# wikiduino-atmega328p.net
KiCad netlist of a schematic drawn in Altium Designer
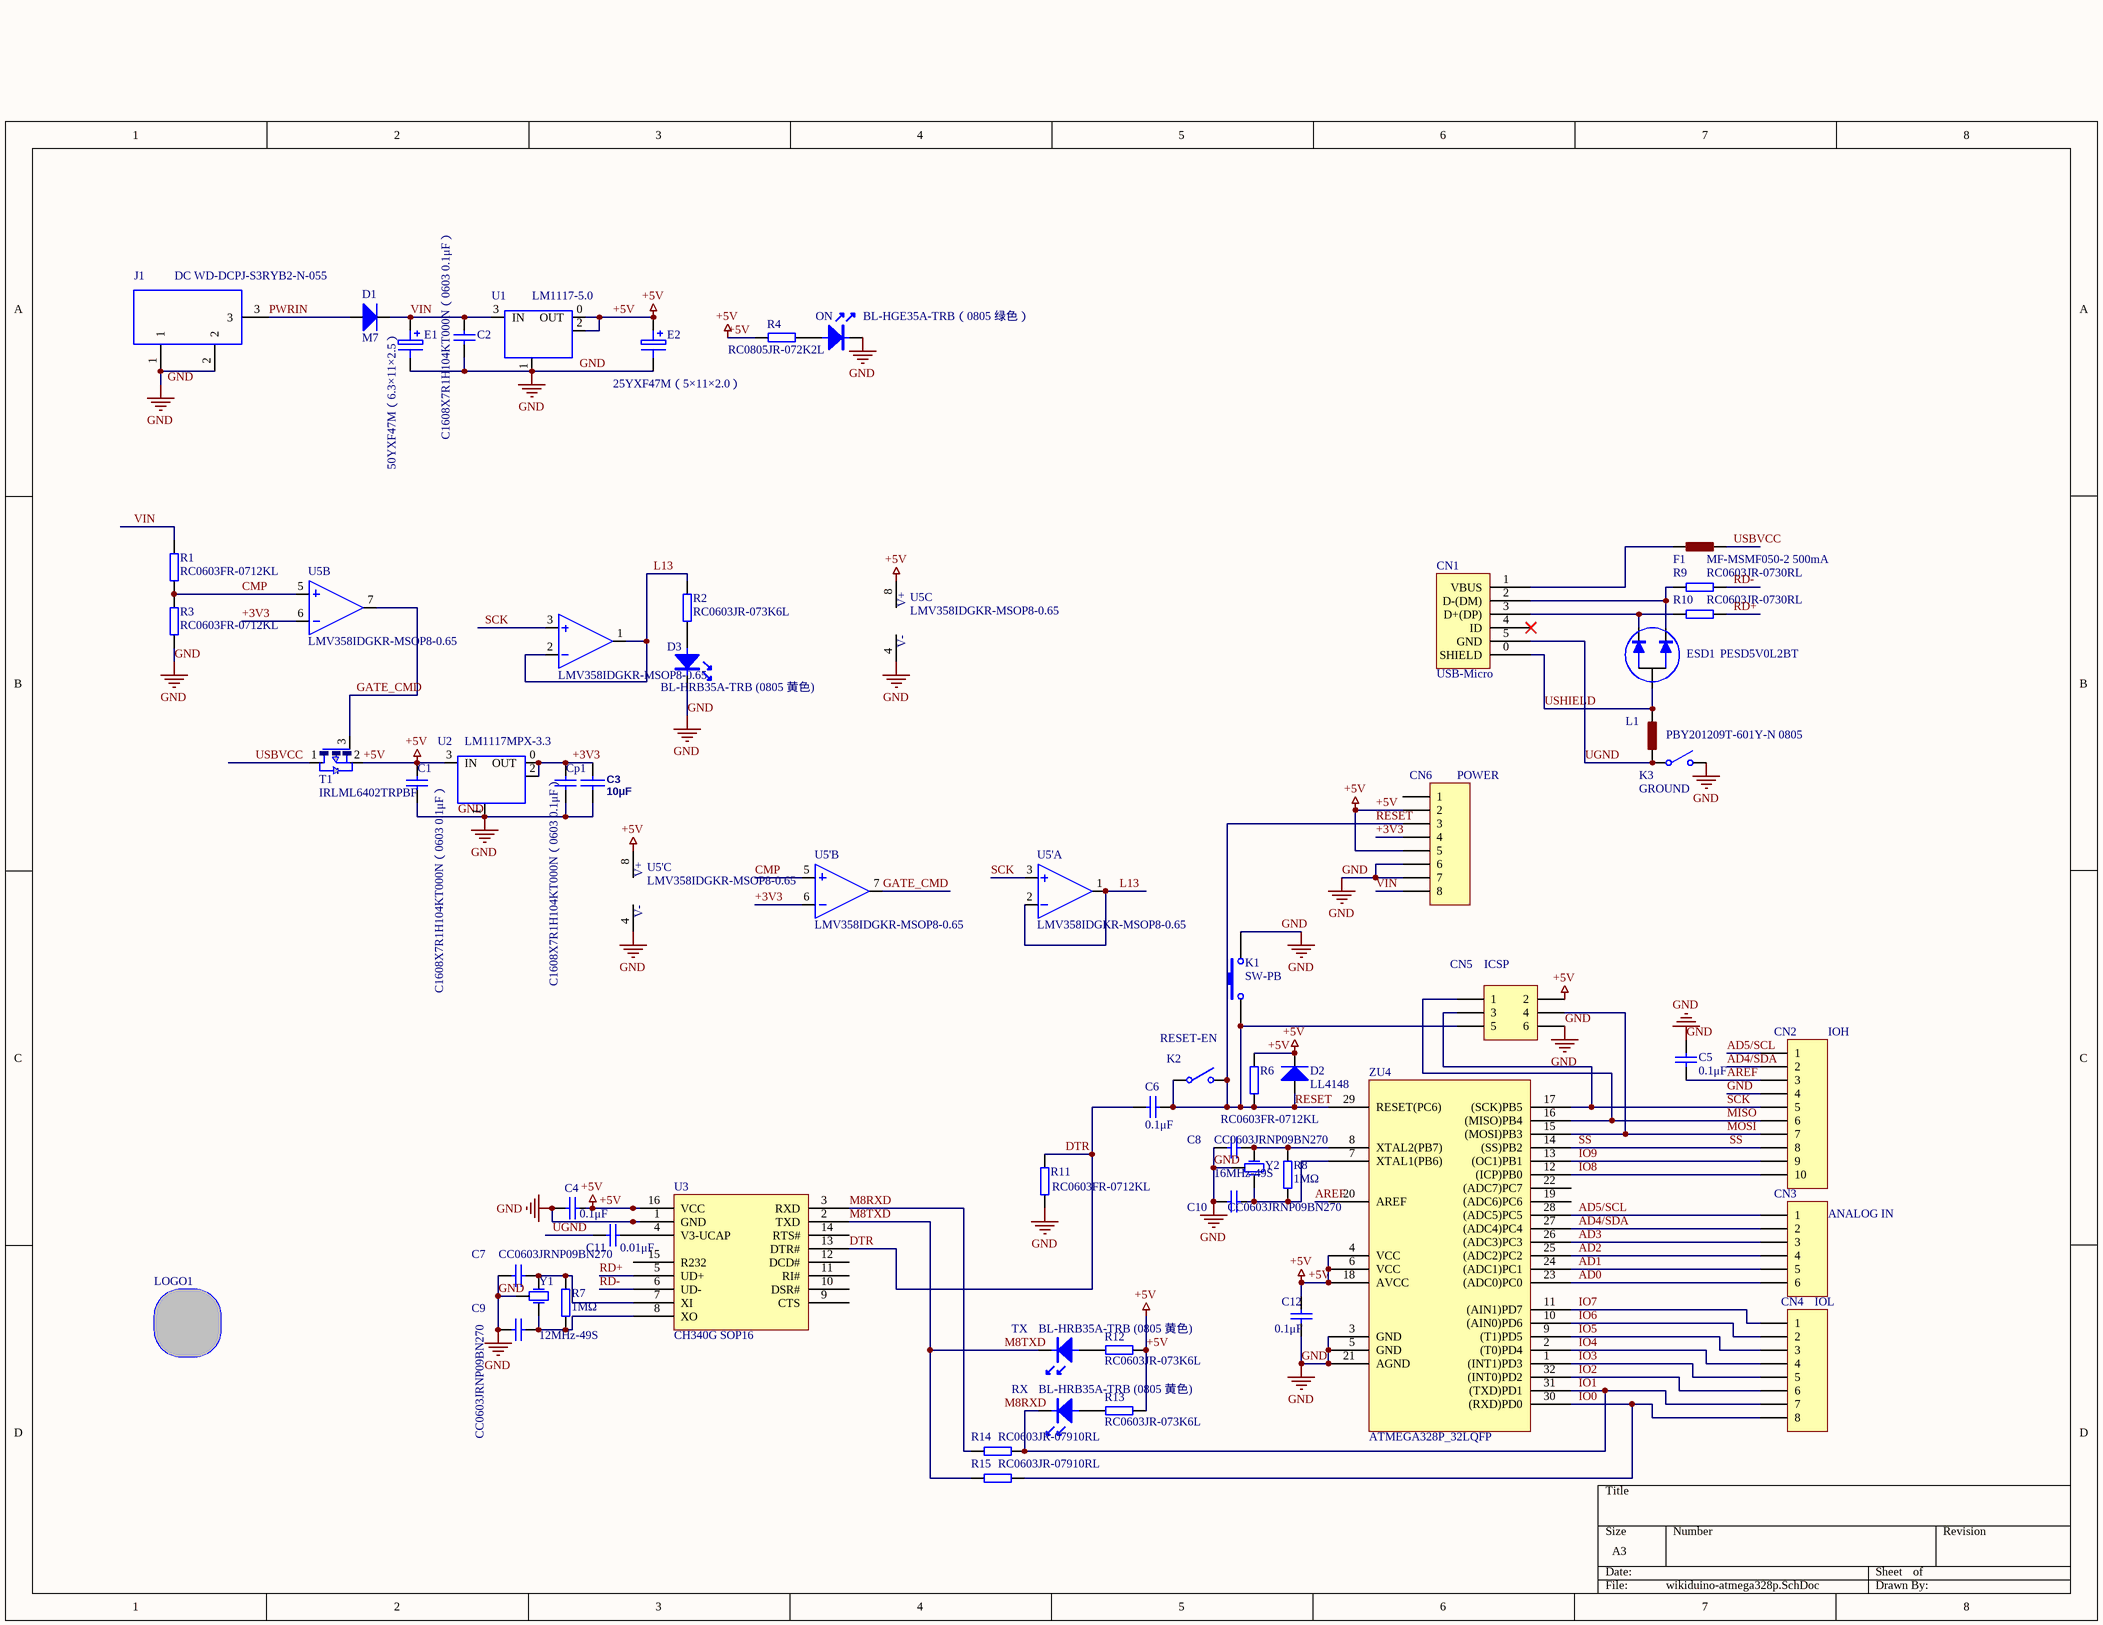
[diagram p0: wikiduino-atmega328p.SchDoc]

(export (version "E")
  (design (tool "Eeschema 10.0.6"))
  (components
    (comp (ref "C1")
      (value "C1608X7R1H104KT000N（0603 0.1μF）")
      (footprint "0603C")
      (description "Capacitor")
      (fields (field (name "PUBLISHER") "Altium Limited"))
      (libsource (lib "*") (part "Cap"))
    )
    (comp (ref "C2")
      (value "C1608X7R1H104KT000N（0603 0.1μF）")
      (footprint "0603C")
      (description "Capacitor")
      (fields (field (name "PUBLISHER") "Altium Limited"))
      (libsource (lib "Miscellaneous Devices") (part "Cap"))
    )
    (comp (ref "C3")
      (value "10μF")
      (footprint "1206C")
      (description "Capacitor")
      (libsource (lib "*") (part "CAP"))
    )
    (comp (ref "C4")
      (value "0.1μF")
      (footprint "0603C")
      (description "Capacitor")
      (fields (field (name "PUBLISHER") "Altium Limited"))
      (libsource (lib "Miscellaneous Devices") (part "Cap"))
    )
    (comp (ref "C5")
      (value "0.1μF")
      (footprint "0603C")
      (description "Capacitor")
      (fields (field (name "PUBLISHER") "Altium Limited"))
      (libsource (lib "Miscellaneous Devices") (part "Cap"))
    )
    (comp (ref "C6")
      (value "0.1μF")
      (footprint "0603C")
      (description "Capacitor")
      (fields (field (name "PUBLISHER") "Altium Limited"))
      (libsource (lib "Miscellaneous Devices") (part "Cap"))
    )
    (comp (ref "C7")
      (value "CC0603JRNP09BN270")
      (footprint "0603C")
      (description "Capacitor")
      (fields (field (name "PUBLISHER") "Altium Limited"))
      (libsource (lib "Miscellaneous Devices") (part "Cap"))
    )
    (comp (ref "C8")
      (value "CC0603JRNP09BN270")
      (footprint "0603C")
      (description "Capacitor")
      (fields (field (name "PUBLISHER") "Altium Limited"))
      (libsource (lib "Miscellaneous Devices") (part "Cap"))
    )
    (comp (ref "C9")
      (value "CC0603JRNP09BN270")
      (footprint "0603C")
      (description "Capacitor")
      (fields (field (name "PUBLISHER") "Altium Limited"))
      (libsource (lib "Miscellaneous Devices") (part "Cap"))
    )
    (comp (ref "C10")
      (value "CC0603JRNP09BN270")
      (footprint "0603C")
      (description "Capacitor")
      (fields (field (name "PUBLISHER") "Altium Limited"))
      (libsource (lib "Miscellaneous Devices") (part "Cap"))
    )
    (comp (ref "C11")
      (value "0.01μF")
      (footprint "0603C")
      (description "Capacitor")
      (fields (field (name "PUBLISHER") "Altium Limited"))
      (libsource (lib "Miscellaneous Devices") (part "Cap"))
    )
    (comp (ref "C12")
      (value "0.1μF")
      (footprint "0603C")
      (description "Capacitor")
      (fields (field (name "PUBLISHER") "Altium Limited"))
      (libsource (lib "Miscellaneous Devices") (part "Cap"))
    )
    (comp (ref "CN1")
      (value "USB-Micro")
      (footprint "USB_MICRO_5S_B")
      (libsource (lib "Connector") (part "USB-Micro"))
    )
    (comp (ref "CN2")
      (value "IOH")
      (footprint "HDR1X10Z")
      (description "Header, 10-Pin")
      (fields (field (name "PUBLISHER") "Altium Limited"))
      (libsource (lib "Miscellaneous Connectors") (part "Header 10"))
    )
    (comp (ref "CN3")
      (value "ANALOG IN")
      (footprint "HDR1X6Z")
      (description "Header, 6-Pin")
      (fields (field (name "PUBLISHER") "Altium Limited"))
      (libsource (lib "Miscellaneous Connectors") (part "Header 6"))
    )
    (comp (ref "CN4")
      (value "IOL")
      (footprint "HDR1X8Z")
      (description "Header, 8-Pin")
      (fields (field (name "PUBLISHER") "Altium Limited"))
      (libsource (lib "Miscellaneous Connectors") (part "Header 8"))
    )
    (comp (ref "CN5")
      (value "ICSP")
      (footprint "HDR2X3")
      (description "Header, 3-Pin, Dual row")
      (fields (field (name "PUBLISHER") "Altium Limited"))
      (libsource (lib "Miscellaneous Connectors") (part "Header 3X2"))
    )
    (comp (ref "CN6")
      (value "POWER")
      (footprint "HDR1X8Z")
      (description "Header, 8-Pin")
      (fields (field (name "PUBLISHER") "Altium Limited"))
      (libsource (lib "Miscellaneous Connectors") (part "Header 8"))
    )
    (comp (ref "Cp1")
      (value "C1608X7R1H104KT000N（0603 0.1μF）")
      (footprint "0603C")
      (description "Capacitor")
      (fields (field (name "PUBLISHER") "Altium Limited"))
      (libsource (lib "*") (part "Cap"))
    )
    (comp (ref "D1")
      (value "M7")
      (footprint "M7")
      (description "D")
      (libsource (lib "Miscellaneous Devices") (part "M7"))
    )
    (comp (ref "D2")
      (value "LL4148")
      (footprint "D1206")
      (description "D")
      (libsource (lib "Miscellaneous Devices") (part "M7"))
    )
    (comp (ref "D3")
      (value "BL-HRB35A-TRB (0805 黄色)")
      (footprint "LED0805-Y")
      (libsource (lib "Miscellaneous Devices") (part "LED"))
    )
    (comp (ref "E1")
      (value "50YXF47M（6.3×11×2.5）")
      (footprint "RB 6.3×11×2.5")
      (libsource (lib "Miscellaneous Devices") (part "E"))
    )
    (comp (ref "E2")
      (value "25YXF47M（5×11×2.0）")
      (footprint "RB 6.3×11×2.5")
      (libsource (lib "Miscellaneous Devices") (part "E"))
    )
    (comp (ref "ESD1")
      (value "PESD5V0L2BT")
      (footprint "SOT-23")
      (libsource (lib "Miscellaneous Devices") (part "ESD1"))
    )
    (comp (ref "F1")
      (value "MF-MSMF050-2 500mA")
      (footprint "L1206")
      (description "BLM21")
      (libsource (lib "") (part "L_1"))
    )
    (comp (ref "J1")
      (value "DC WD-DCPJ-S3RYB2-N-055")
      (footprint "DC_IN")
      (description "POWERSUPPLY_DC21MMX")
      (libsource (lib "Miscellaneous Connectors") (part "DC_IN"))
    )
    (comp (ref "K1")
      (value "SW-PB")
      (footprint "按钮/SO")
      (description "Switch")
      (fields (field (name "PUBLISHER") "Altium Limited"))
      (libsource (lib "Miscellaneous Devices") (part "SW-PB"))
    )
    (comp (ref "K2")
      (value "RESET-EN")
      (footprint "0101")
      (description "Single-Pole, Single-Throw Switch")
      (fields (field (name "PUBLISHER") "Altium Limited"))
      (libsource (lib "Miscellaneous Devices") (part "SW-SPST"))
    )
    (comp (ref "K3")
      (value "GROUND")
      (footprint "0101")
      (description "Single-Pole, Single-Throw Switch")
      (fields (field (name "PUBLISHER") "Altium Limited"))
      (libsource (lib "Miscellaneous Devices") (part "SW-SPST"))
    )
    (comp (ref "L1")
      (value "PBY201209T-601Y-N 0805")
      (footprint "L0805")
      (description "BLM21")
      (libsource (lib "Miscellaneous Devices") (part "L"))
    )
    (comp (ref "LOGO1")
      (value "LOGO")
      (footprint "USB_LOGO")
      (libsource (lib "Miscellaneous Connectors") (part "LOGO"))
    )
    (comp (ref "ON")
      (value "BL-HGE35A-TRB（0805 绿色）")
      (footprint "LED0805-R")
      (libsource (lib "Miscellaneous Devices") (part "LED"))
    )
    (comp (ref "R1")
      (value "RC0603FR-0712KL")
      (footprint "0603R")
      (description "Resistor")
      (libsource (lib "Miscellaneous Devices") (part "R"))
    )
    (comp (ref "R2")
      (value "RC0603JR-073K6L")
      (footprint "0603R")
      (description "Resistor")
      (libsource (lib "Miscellaneous Devices") (part "R"))
    )
    (comp (ref "R3")
      (value "RC0603FR-0712KL")
      (footprint "0603R")
      (description "Resistor")
      (libsource (lib "Miscellaneous Devices") (part "R"))
    )
    (comp (ref "R4")
      (value "RC0805JR-072K2L")
      (footprint "0805/R")
      (description "Resistor")
      (libsource (lib "Miscellaneous Devices") (part "R"))
    )
    (comp (ref "R6")
      (value "RC0603FR-0712KL")
      (footprint "0603R")
      (description "Resistor")
      (libsource (lib "Miscellaneous Devices") (part "R"))
    )
    (comp (ref "R7")
      (value "1MΩ")
      (footprint "0603R")
      (description "Resistor")
      (libsource (lib "Miscellaneous Devices") (part "R"))
    )
    (comp (ref "R8")
      (value "1MΩ")
      (footprint "0603R")
      (description "Resistor")
      (libsource (lib "Miscellaneous Devices") (part "R"))
    )
    (comp (ref "R9")
      (value "RC0603JR-0730RL")
      (footprint "0603R")
      (description "Resistor")
      (libsource (lib "Miscellaneous Devices") (part "R"))
    )
    (comp (ref "R10")
      (value "RC0603JR-0730RL")
      (footprint "0603R")
      (description "Resistor")
      (libsource (lib "Miscellaneous Devices") (part "R"))
    )
    (comp (ref "R11")
      (value "RC0603FR-0712KL")
      (footprint "0603R")
      (description "Resistor")
      (libsource (lib "Miscellaneous Devices") (part "R"))
    )
    (comp (ref "R12")
      (value "RC0603JR-073K6L")
      (footprint "0603R")
      (description "Resistor")
      (libsource (lib "Miscellaneous Devices") (part "R"))
    )
    (comp (ref "R13")
      (value "RC0603JR-073K6L")
      (footprint "0603R")
      (description "Resistor")
      (libsource (lib "Miscellaneous Devices") (part "R"))
    )
    (comp (ref "R14")
      (value "RC0603JR-07910RL")
      (footprint "0603R")
      (description "Resistor")
      (libsource (lib "Miscellaneous Devices") (part "R"))
    )
    (comp (ref "R15")
      (value "RC0603JR-07910RL")
      (footprint "0603R")
      (description "Resistor")
      (libsource (lib "Miscellaneous Devices") (part "R"))
    )
    (comp (ref "RX")
      (value "BL-HRB35A-TRB (0805 黄色)")
      (footprint "LED0805-Y")
      (libsource (lib "Miscellaneous Devices") (part "LED"))
    )
    (comp (ref "T1")
      (value "IRLML6402TRPBF")
      (footprint "MOSFET")
      (libsource (lib "Miscellaneous Devices") (part "PMOSSOT23"))
    )
    (comp (ref "TX")
      (value "BL-HRB35A-TRB (0805 黄色)")
      (footprint "LED0805-Y")
      (libsource (lib "Miscellaneous Devices") (part "LED"))
    )
    (comp (ref "U1")
      (value "LM1117-5.0")
      (footprint "SOT223")
      (libsource (lib "Miscellaneous Devices") (part "LM1117"))
    )
    (comp (ref "U2")
      (value "LM1117MPX-3.3")
      (footprint "SOT223")
      (libsource (lib "Miscellaneous Devices") (part "LM1117"))
    )
    (comp (ref "U3")
      (value "CH340G SOP16")
      (footprint "SO-16")
      (libsource (lib "Miscellaneous Devices") (part "CH340G"))
    )
    (comp (ref "U5")
      (value "LMV358IDGKR-MSOP8-0.65")
      (footprint "MSOP8-0.65")
      (libsource (lib "wikiduino-atmega328p") (part "LMV358MMX"))
    )
    (comp (ref "U5'")
      (value "LMV358IDGKR-MSOP8-0.65")
      (footprint "so-8")
      (libsource (lib "wikiduino-atmega328p") (part "LMV358MMX"))
    )
    (comp (ref "Y1")
      (value "12MHz-49S")
      (footprint "XTAL-49S")
      (description "3pXTAL")
      (libsource (lib "Miscellaneous Devices") (part "XTAL1"))
    )
    (comp (ref "Y2")
      (value "16MHz-49S")
      (footprint "XTAL-49S")
      (description "3pXTAL")
      (libsource (lib "Miscellaneous Devices") (part "XTAL1"))
    )
    (comp (ref "ZU4")
      (value "ATMEGA328P_32LQFP")
      (footprint "LQFP32")
      (description "Arduino ATMEGA328P")
      (libsource (lib "Miscellaneous Devices") (part "ATMEGA328P_32LQFP"))
    )
  )
  (nets
    (net (code "1") (name "+5V") (class "Default")
      (node (ref "C1") (pin "1") (pinfunction "1_1") (pintype "passive"))
      (node (ref "C12") (pin "2") (pinfunction "2_2") (pintype "passive"))
      (node (ref "C4") (pin "2") (pinfunction "2_2") (pintype "passive"))
      (node (ref "CN5") (pin "2") (pinfunction "2_2") (pintype "passive"))
      (node (ref "CN6") (pin "2") (pinfunction "2_2") (pintype "passive"))
      (node (ref "CN6") (pin "5") (pinfunction "5_5") (pintype "passive"))
      (node (ref "D2") (pin "K") (pinfunction "K_K") (pintype "passive"))
      (node (ref "E2") (pin "1") (pintype "passive"))
      (node (ref "R12") (pin "1") (pintype "passive"))
      (node (ref "R13") (pin "1") (pintype "passive"))
      (node (ref "R4") (pin "2") (pintype "passive"))
      (node (ref "R6") (pin "1") (pintype "passive"))
      (node (ref "T1") (pin "2") (pinfunction "S_2") (pintype "passive"))
      (node (ref "U1") (pin "0") (pinfunction "OUT_0") (pintype "passive"))
      (node (ref "U1") (pin "2") (pinfunction "OUT@1_2") (pintype "passive"))
      (node (ref "U2") (pin "3") (pinfunction "IN_3") (pintype "passive"))
      (node (ref "U3") (pin "16") (pinfunction "VCC_16") (pintype "passive"))
      (node (ref "U5") (pin "8") (pinfunction "V+_8") (pintype "passive"))
      (node (ref "U5'") (pin "8") (pinfunction "V+_8") (pintype "passive"))
      (node (ref "ZU4") (pin "18") (pinfunction "AVCC_18") (pintype "passive"))
      (node (ref "ZU4") (pin "4") (pinfunction "VCC_4") (pintype "passive"))
      (node (ref "ZU4") (pin "6") (pinfunction "VCC_6") (pintype "passive"))
    )
    (net (code "2") (name "/+3V3") (class "Default")
      (node (ref "C3") (pin "2") (pinfunction "2_2") (pintype "passive"))
      (node (ref "CN6") (pin "4") (pinfunction "4_4") (pintype "passive"))
      (node (ref "Cp1") (pin "1") (pinfunction "1_1") (pintype "passive"))
      (node (ref "U2") (pin "0") (pinfunction "OUT_0") (pintype "passive"))
      (node (ref "U2") (pin "2") (pinfunction "OUT@1_2") (pintype "passive"))
      (node (ref "U5") (pin "6") (pinfunction "-IN_6") (pintype "passive"))
      (node (ref "U5'") (pin "6") (pinfunction "-IN_6") (pintype "passive"))
    )
    (net (code "3") (name "/AD0") (class "Default")
      (node (ref "CN3") (pin "6") (pinfunction "6_6") (pintype "passive"))
      (node (ref "ZU4") (pin "23") (pinfunction "(ADC0)PC0_23") (pintype "passive"))
    )
    (net (code "4") (name "/AD1") (class "Default")
      (node (ref "CN3") (pin "5") (pinfunction "5_5") (pintype "passive"))
      (node (ref "ZU4") (pin "24") (pinfunction "(ADC1)PC1_24") (pintype "passive"))
    )
    (net (code "5") (name "/AD2") (class "Default")
      (node (ref "CN3") (pin "4") (pinfunction "4_4") (pintype "passive"))
      (node (ref "ZU4") (pin "25") (pinfunction "(ADC2)PC2_25") (pintype "passive"))
    )
    (net (code "6") (name "/AD3") (class "Default")
      (node (ref "CN3") (pin "3") (pinfunction "3_3") (pintype "passive"))
      (node (ref "ZU4") (pin "26") (pinfunction "(ADC3)PC3_26") (pintype "passive"))
    )
    (net (code "7") (name "/AD4{slash}SDA") (class "Default")
      (node (ref "CN2") (pin "2") (pinfunction "2_2") (pintype "passive"))
      (node (ref "CN3") (pin "2") (pinfunction "2_2") (pintype "passive"))
      (node (ref "ZU4") (pin "27") (pinfunction "(ADC4)PC4_27") (pintype "passive"))
    )
    (net (code "8") (name "/AD5{slash}SCL") (class "Default")
      (node (ref "CN2") (pin "1") (pinfunction "1_1") (pintype "passive"))
      (node (ref "CN3") (pin "1") (pinfunction "1_1") (pintype "passive"))
      (node (ref "ZU4") (pin "28") (pinfunction "(ADC5)PC5_28") (pintype "passive"))
    )
    (net (code "9") (name "/AREF") (class "Default")
      (node (ref "C5") (pin "1") (pinfunction "1_1") (pintype "passive"))
      (node (ref "CN2") (pin "3") (pinfunction "3_3") (pintype "passive"))
      (node (ref "ZU4") (pin "20") (pinfunction "AREF_20") (pintype "passive"))
    )
    (net (code "10") (name "/CMP") (class "Default")
      (node (ref "R1") (pin "2") (pintype "passive"))
      (node (ref "R3") (pin "1") (pintype "passive"))
      (node (ref "U5") (pin "5") (pinfunction "+IN_5") (pintype "passive"))
      (node (ref "U5'") (pin "5") (pinfunction "+IN_5") (pintype "passive"))
    )
    (net (code "11") (name "/DTR") (class "Default")
      (node (ref "C6") (pin "1") (pinfunction "1_1") (pintype "passive"))
      (node (ref "R11") (pin "1") (pintype "passive"))
      (node (ref "U3") (pin "13") (pinfunction "DTR#_13") (pintype "passive"))
    )
    (net (code "12") (name "/GATE_CMD") (class "Default")
      (node (ref "T1") (pin "3") (pinfunction "G_3") (pintype "passive"))
      (node (ref "U5") (pin "7") (pinfunction "OUT_7") (pintype "passive"))
      (node (ref "U5'") (pin "7") (pinfunction "OUT_7") (pintype "passive"))
    )
    (net (code "13") (name "/IO0") (class "Default")
      (node (ref "CN4") (pin "8") (pinfunction "8_8") (pintype "passive"))
      (node (ref "R15") (pin "1") (pintype "passive"))
      (node (ref "ZU4") (pin "30") (pinfunction "(RXD)PD0_30") (pintype "passive"))
    )
    (net (code "14") (name "/IO1") (class "Default")
      (node (ref "CN4") (pin "7") (pinfunction "7_7") (pintype "passive"))
      (node (ref "R14") (pin "1") (pintype "passive"))
      (node (ref "RX") (pin "K") (pintype "passive"))
      (node (ref "ZU4") (pin "31") (pinfunction "(TXD)PD1_31") (pintype "passive"))
    )
    (net (code "15") (name "/IO2") (class "Default")
      (node (ref "CN4") (pin "6") (pinfunction "6_6") (pintype "passive"))
      (node (ref "ZU4") (pin "32") (pinfunction "(INT0)PD2_32") (pintype "passive"))
    )
    (net (code "16") (name "/IO3") (class "Default")
      (node (ref "CN4") (pin "5") (pinfunction "5_5") (pintype "passive"))
      (node (ref "ZU4") (pin "1") (pinfunction "(INT1)PD3_1") (pintype "passive"))
    )
    (net (code "17") (name "/IO4") (class "Default")
      (node (ref "CN4") (pin "4") (pinfunction "4_4") (pintype "passive"))
      (node (ref "ZU4") (pin "2") (pinfunction "(T0)PD4_2") (pintype "passive"))
    )
    (net (code "18") (name "/IO5") (class "Default")
      (node (ref "CN4") (pin "3") (pinfunction "3_3") (pintype "passive"))
      (node (ref "ZU4") (pin "9") (pinfunction "(T1)PD5_9") (pintype "passive"))
    )
    (net (code "19") (name "/IO6") (class "Default")
      (node (ref "CN4") (pin "2") (pinfunction "2_2") (pintype "passive"))
      (node (ref "ZU4") (pin "10") (pinfunction "(AIN0)PD6_10") (pintype "passive"))
    )
    (net (code "20") (name "/IO7") (class "Default")
      (node (ref "CN4") (pin "1") (pinfunction "1_1") (pintype "passive"))
      (node (ref "ZU4") (pin "11") (pinfunction "(AIN1)PD7_11") (pintype "passive"))
    )
    (net (code "21") (name "/IO8") (class "Default")
      (node (ref "CN2") (pin "10") (pinfunction "10_10") (pintype "passive"))
      (node (ref "ZU4") (pin "12") (pinfunction "(ICP)PB0_12") (pintype "passive"))
    )
    (net (code "22") (name "/IO9") (class "Default")
      (node (ref "CN2") (pin "9") (pinfunction "9_9") (pintype "passive"))
      (node (ref "ZU4") (pin "13") (pinfunction "(OC1)PB1_13") (pintype "passive"))
    )
    (net (code "23") (name "/L13") (class "Default")
      (node (ref "R2") (pin "1") (pintype "passive"))
      (node (ref "U5") (pin "1") (pinfunction "OUT_1") (pintype "passive"))
      (node (ref "U5") (pin "2") (pinfunction "-IN_2") (pintype "passive"))
      (node (ref "U5'") (pin "1") (pinfunction "OUT_1") (pintype "passive"))
      (node (ref "U5'") (pin "2") (pinfunction "-IN_2") (pintype "passive"))
    )
    (net (code "24") (name "/M8RXD") (class "Default")
      (node (ref "R14") (pin "2") (pintype "passive"))
      (node (ref "U3") (pin "3") (pinfunction "RXD_3") (pintype "passive"))
    )
    (net (code "25") (name "/M8TXD") (class "Default")
      (node (ref "R15") (pin "2") (pintype "passive"))
      (node (ref "TX") (pin "K") (pintype "passive"))
      (node (ref "U3") (pin "2") (pinfunction "TXD_2") (pintype "passive"))
    )
    (net (code "26") (name "/MISO") (class "Default")
      (node (ref "CN2") (pin "6") (pinfunction "6_6") (pintype "passive"))
      (node (ref "CN5") (pin "1") (pinfunction "1_1") (pintype "passive"))
      (node (ref "ZU4") (pin "16") (pinfunction "(MISO)PB4_16") (pintype "passive"))
    )
    (net (code "27") (name "/MOSI") (class "Default")
      (node (ref "CN2") (pin "7") (pinfunction "7_7") (pintype "passive"))
      (node (ref "CN5") (pin "4") (pinfunction "4_4") (pintype "passive"))
      (node (ref "ZU4") (pin "15") (pinfunction "(MOSI)PB3_15") (pintype "passive"))
    )
    (net (code "28") (name "/PWRIN") (class "Default")
      (node (ref "D1") (pin "A") (pinfunction "A_A") (pintype "passive"))
      (node (ref "J1") (pin "3") (pinfunction "3_3") (pintype "passive"))
    )
    (net (code "29") (name "/RD+") (class "Default")
      (node (ref "R10") (pin "1") (pintype "passive"))
      (node (ref "U3") (pin "5") (pinfunction "UD+_5") (pintype "passive"))
    )
    (net (code "30") (name "/RD-") (class "Default")
      (node (ref "R9") (pin "1") (pintype "passive"))
      (node (ref "U3") (pin "6") (pinfunction "UD-_6") (pintype "passive"))
    )
    (net (code "31") (name "/RESET") (class "Default")
      (node (ref "C6") (pin "2") (pinfunction "2_2") (pintype "passive"))
      (node (ref "CN5") (pin "5") (pinfunction "5_5") (pintype "passive"))
      (node (ref "CN6") (pin "3") (pinfunction "3_3") (pintype "passive"))
      (node (ref "D2") (pin "A") (pinfunction "A_A") (pintype "passive"))
      (node (ref "K1") (pin "1") (pinfunction "1_1") (pintype "passive"))
      (node (ref "K2") (pin "1") (pinfunction "COMMON_1") (pintype "passive"))
      (node (ref "K2") (pin "2") (pinfunction "NO_2") (pintype "passive"))
      (node (ref "R6") (pin "2") (pintype "passive"))
      (node (ref "ZU4") (pin "29") (pinfunction "RESET(PC6)_29") (pintype "passive"))
    )
    (net (code "32") (name "/SCK") (class "Default")
      (node (ref "CN2") (pin "5") (pinfunction "5_5") (pintype "passive"))
      (node (ref "CN5") (pin "3") (pinfunction "3_3") (pintype "passive"))
      (node (ref "U5") (pin "3") (pinfunction "+IN_3") (pintype "passive"))
      (node (ref "U5'") (pin "3") (pinfunction "+IN_3") (pintype "passive"))
      (node (ref "ZU4") (pin "17") (pinfunction "(SCK)PB5_17") (pintype "passive"))
    )
    (net (code "33") (name "/SS") (class "Default")
      (node (ref "CN2") (pin "8") (pinfunction "8_8") (pintype "passive"))
      (node (ref "ZU4") (pin "14") (pinfunction "(SS)PB2_14") (pintype "passive"))
    )
    (net (code "34") (name "/UGND") (class "Default")
      (node (ref "C11") (pin "2") (pinfunction "2_2") (pintype "passive"))
      (node (ref "CN1") (pin "5") (pinfunction "GND_5") (pintype "passive"))
      (node (ref "K3") (pin "1") (pinfunction "COMMON_1") (pintype "passive"))
      (node (ref "L1") (pin "2") (pintype "passive"))
    )
    (net (code "35") (name "/USBVCC") (class "Default")
      (node (ref "F1") (pin "1") (pintype "passive"))
      (node (ref "T1") (pin "1") (pinfunction "D_1") (pintype "passive"))
    )
    (net (code "36") (name "/USHIELD") (class "Default")
      (node (ref "CN1") (pin "0") (pinfunction "SHIELD_0") (pintype "passive"))
      (node (ref "ESD1") (pin "3") (pinfunction "3_3") (pintype "passive"))
      (node (ref "L1") (pin "1") (pintype "passive"))
    )
    (net (code "37") (name "/VIN") (class "Default")
      (node (ref "C2") (pin "2") (pinfunction "2_2") (pintype "passive"))
      (node (ref "CN6") (pin "8") (pinfunction "8_8") (pintype "passive"))
      (node (ref "D1") (pin "K") (pinfunction "K_K") (pintype "passive"))
      (node (ref "E1") (pin "1") (pintype "passive"))
      (node (ref "R1") (pin "1") (pintype "passive"))
      (node (ref "U1") (pin "3") (pinfunction "IN_3") (pintype "passive"))
    )
    (net (code "38") (name "GND") (class "Default")
      (node (ref "C1") (pin "2") (pinfunction "2_2") (pintype "passive"))
      (node (ref "C10") (pin "1") (pinfunction "1_1") (pintype "passive"))
      (node (ref "C12") (pin "1") (pinfunction "1_1") (pintype "passive"))
      (node (ref "C2") (pin "1") (pinfunction "1_1") (pintype "passive"))
      (node (ref "C3") (pin "1") (pinfunction "1_1") (pintype "passive"))
      (node (ref "C4") (pin "1") (pinfunction "1_1") (pintype "passive"))
      (node (ref "C5") (pin "2") (pinfunction "2_2") (pintype "passive"))
      (node (ref "C7") (pin "1") (pinfunction "1_1") (pintype "passive"))
      (node (ref "C8") (pin "1") (pinfunction "1_1") (pintype "passive"))
      (node (ref "C9") (pin "1") (pinfunction "1_1") (pintype "passive"))
      (node (ref "CN2") (pin "4") (pinfunction "4_4") (pintype "passive"))
      (node (ref "CN5") (pin "6") (pinfunction "6_6") (pintype "passive"))
      (node (ref "CN6") (pin "6") (pinfunction "6_6") (pintype "passive"))
      (node (ref "CN6") (pin "7") (pinfunction "7_7") (pintype "passive"))
      (node (ref "Cp1") (pin "2") (pinfunction "2_2") (pintype "passive"))
      (node (ref "D3") (pin "K") (pintype "passive"))
      (node (ref "E1") (pin "2") (pintype "passive"))
      (node (ref "E2") (pin "2") (pintype "passive"))
      (node (ref "J1") (pin "1") (pinfunction "1_1") (pintype "passive"))
      (node (ref "J1") (pin "2") (pinfunction "2_2") (pintype "passive"))
      (node (ref "K1") (pin "2") (pinfunction "2_2") (pintype "passive"))
      (node (ref "K3") (pin "2") (pinfunction "NO_2") (pintype "passive"))
      (node (ref "ON") (pin "K") (pintype "passive"))
      (node (ref "R11") (pin "2") (pintype "passive"))
      (node (ref "R3") (pin "2") (pintype "passive"))
      (node (ref "U1") (pin "1") (pinfunction "GND/ADJ_1") (pintype "passive"))
      (node (ref "U2") (pin "1") (pinfunction "GND/ADJ_1") (pintype "passive"))
      (node (ref "U3") (pin "1") (pinfunction "GND_1") (pintype "passive"))
      (node (ref "U5") (pin "4") (pinfunction "V-_4") (pintype "passive"))
      (node (ref "U5'") (pin "4") (pinfunction "V-_4") (pintype "passive"))
      (node (ref "Y1") (pin "3") (pinfunction "3_3") (pintype "passive"))
      (node (ref "Y2") (pin "3") (pinfunction "3_3") (pintype "passive"))
      (node (ref "ZU4") (pin "21") (pinfunction "AGND_21") (pintype "passive"))
      (node (ref "ZU4") (pin "3") (pinfunction "GND_3") (pintype "passive"))
      (node (ref "ZU4") (pin "5") (pinfunction "GND_5") (pintype "passive"))
    )
    (net (code "39") (name "Net-(CN1-D+(DP))") (class "Default")
      (node (ref "CN1") (pin "3") (pinfunction "D+(DP)_3") (pintype "passive"))
      (node (ref "ESD1") (pin "1") (pinfunction "1_1") (pintype "passive"))
      (node (ref "R10") (pin "2") (pintype "passive"))
    )
    (net (code "40") (name "Net-(CN1-D-(DM))") (class "Default")
      (node (ref "CN1") (pin "2") (pinfunction "D-(DM)_2") (pintype "passive"))
      (node (ref "ESD1") (pin "2") (pinfunction "2_2") (pintype "passive"))
      (node (ref "R9") (pin "2") (pintype "passive"))
    )
    (net (code "41") (name "Net-(CN1-VBUS)") (class "Default")
      (node (ref "CN1") (pin "1") (pinfunction "VBUS_1") (pintype "passive"))
      (node (ref "F1") (pin "2") (pintype "passive"))
    )
    (net (code "42") (name "Net-(D3-PadA)") (class "Default")
      (node (ref "D3") (pin "A") (pintype "passive"))
      (node (ref "R2") (pin "2") (pintype "passive"))
    )
    (net (code "43") (name "Net-(ON-PadA)") (class "Default")
      (node (ref "ON") (pin "A") (pintype "passive"))
      (node (ref "R4") (pin "1") (pintype "passive"))
    )
    (net (code "44") (name "Net-(R12-Pad2)") (class "Default")
      (node (ref "R12") (pin "2") (pintype "passive"))
      (node (ref "TX") (pin "A") (pintype "passive"))
    )
    (net (code "45") (name "Net-(R13-Pad2)") (class "Default")
      (node (ref "R13") (pin "2") (pintype "passive"))
      (node (ref "RX") (pin "A") (pintype "passive"))
    )
    (net (code "46") (name "Net-(U3-V3-UCAP)") (class "Default")
      (node (ref "C11") (pin "1") (pinfunction "1_1") (pintype "passive"))
      (node (ref "U3") (pin "4") (pinfunction "V3-UCAP_4") (pintype "passive"))
    )
    (net (code "47") (name "Net-(U3-XI)") (class "Default")
      (node (ref "C7") (pin "2") (pinfunction "2_2") (pintype "passive"))
      (node (ref "R7") (pin "1") (pintype "passive"))
      (node (ref "U3") (pin "7") (pinfunction "XI_7") (pintype "passive"))
      (node (ref "Y1") (pin "1") (pinfunction "OSC1_1") (pintype "passive"))
    )
    (net (code "48") (name "Net-(U3-XO)") (class "Default")
      (node (ref "C9") (pin "2") (pinfunction "2_2") (pintype "passive"))
      (node (ref "R7") (pin "2") (pintype "passive"))
      (node (ref "U3") (pin "8") (pinfunction "XO_8") (pintype "passive"))
      (node (ref "Y1") (pin "2") (pinfunction "OSC2_2") (pintype "passive"))
    )
    (net (code "49") (name "Net-(Y2-OSC1)") (class "Default")
      (node (ref "C8") (pin "2") (pinfunction "2_2") (pintype "passive"))
      (node (ref "R8") (pin "1") (pintype "passive"))
      (node (ref "Y2") (pin "1") (pinfunction "OSC1_1") (pintype "passive"))
      (node (ref "ZU4") (pin "8") (pinfunction "XTAL2(PB7)_8") (pintype "passive"))
    )
    (net (code "50") (name "Net-(Y2-OSC2)") (class "Default")
      (node (ref "C10") (pin "2") (pinfunction "2_2") (pintype "passive"))
      (node (ref "R8") (pin "2") (pintype "passive"))
      (node (ref "Y2") (pin "2") (pinfunction "OSC2_2") (pintype "passive"))
      (node (ref "ZU4") (pin "7") (pinfunction "XTAL1(PB6)_7") (pintype "passive"))
    )
    (net (code "51") (name "unconnected-(CN1-ID-Pad4)") (class "Default")
      (node (ref "CN1") (pin "4") (pinfunction "ID_4") (pintype "passive+no_connect"))
    )
    (net (code "52") (name "unconnected-(CN6-Pad1)") (class "Default")
      (node (ref "CN6") (pin "1") (pinfunction "1_1") (pintype "passive"))
    )
    (net (code "53") (name "unconnected-(U3-CTS-Pad9)") (class "Default")
      (node (ref "U3") (pin "9") (pinfunction "CTS_9") (pintype "passive"))
    )
    (net (code "54") (name "unconnected-(U3-DCD#-Pad12)") (class "Default")
      (node (ref "U3") (pin "12") (pinfunction "DCD#_12") (pintype "passive"))
    )
    (net (code "55") (name "unconnected-(U3-DSR#-Pad10)") (class "Default")
      (node (ref "U3") (pin "10") (pinfunction "DSR#_10") (pintype "passive"))
    )
    (net (code "56") (name "unconnected-(U3-R232-Pad15)") (class "Default")
      (node (ref "U3") (pin "15") (pinfunction "R232_15") (pintype "passive"))
    )
    (net (code "57") (name "unconnected-(U3-RI#-Pad11)") (class "Default")
      (node (ref "U3") (pin "11") (pinfunction "RI#_11") (pintype "passive"))
    )
    (net (code "58") (name "unconnected-(U3-RTS#-Pad14)") (class "Default")
      (node (ref "U3") (pin "14") (pinfunction "RTS#_14") (pintype "passive"))
    )
    (net (code "59") (name "unconnected-(ZU4-(ADC6)PC6-Pad19)") (class "Default")
      (node (ref "ZU4") (pin "19") (pinfunction "(ADC6)PC6_19") (pintype "passive"))
    )
    (net (code "60") (name "unconnected-(ZU4-(ADC7)PC7-Pad22)") (class "Default")
      (node (ref "ZU4") (pin "22") (pinfunction "(ADC7)PC7_22") (pintype "passive"))
    )
  )
)
